# red2.net
KiCad netlist of a schematic drawn in EAGLE
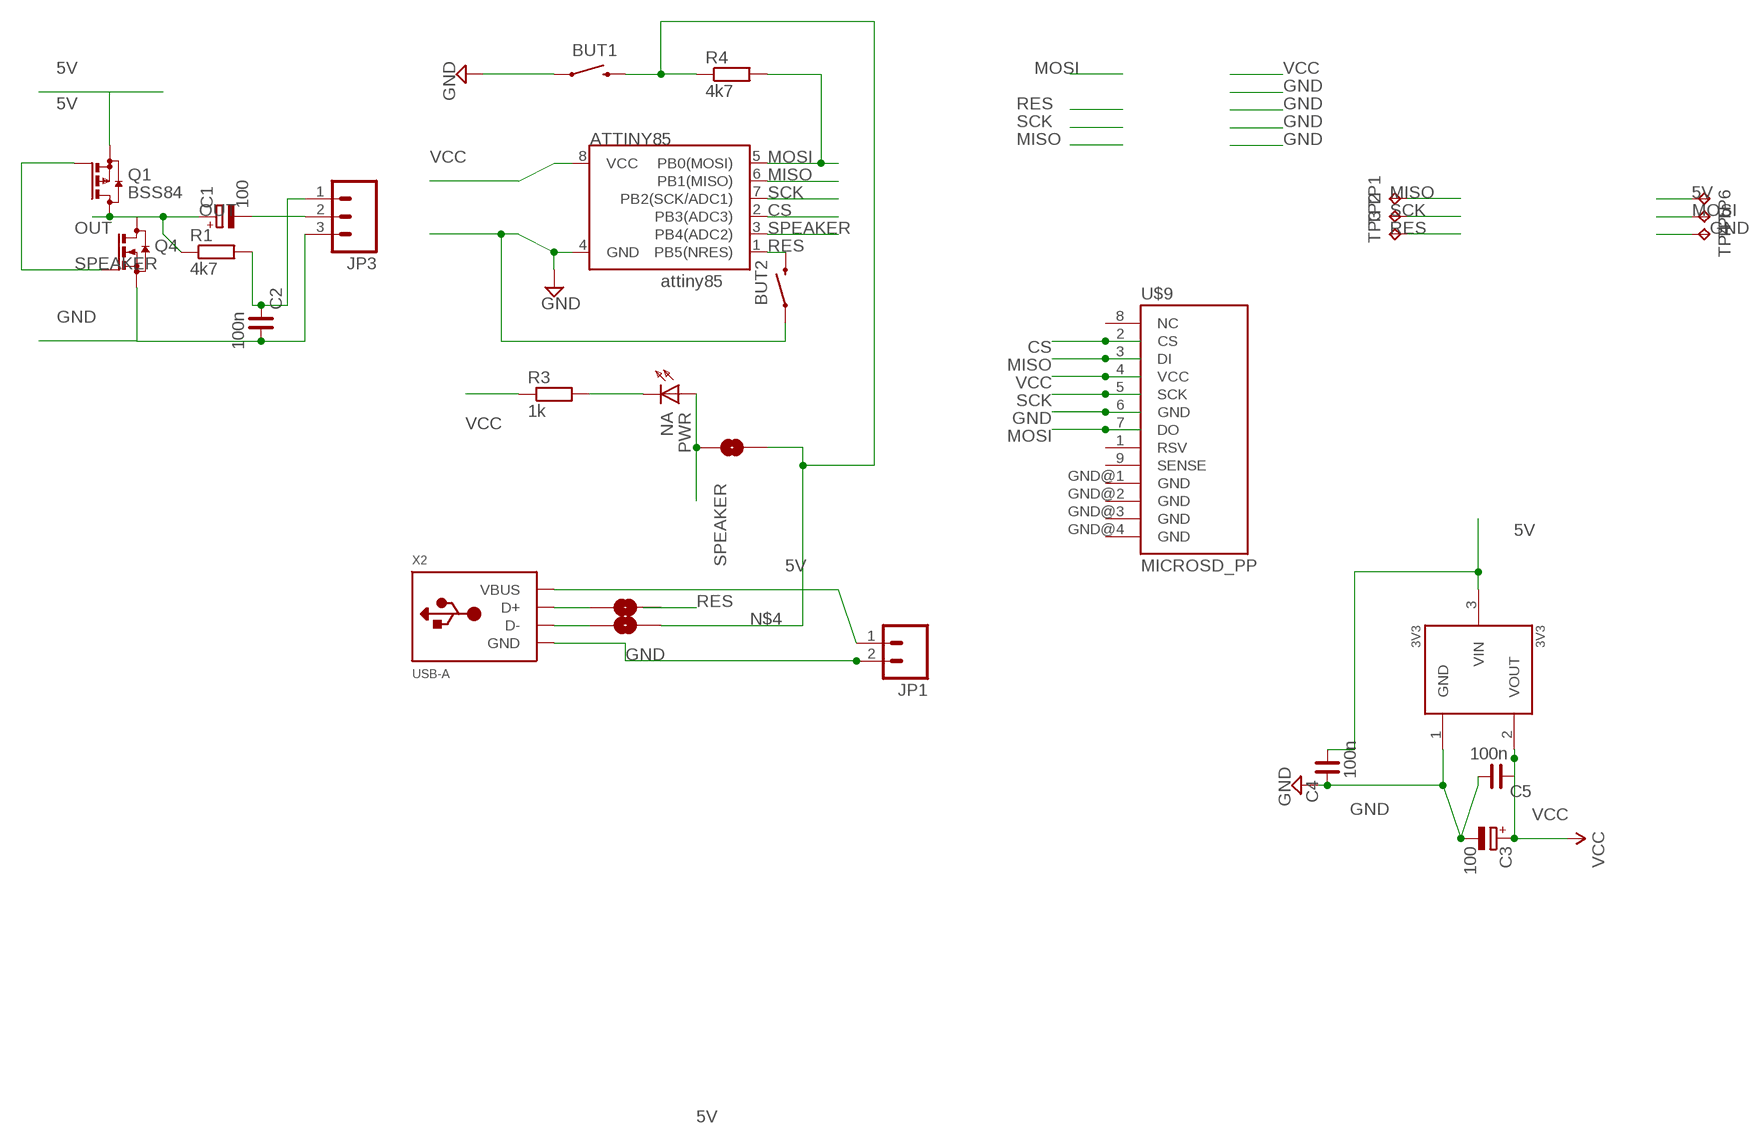
[diagram p0: schematic, sheet 1]

(export (version "E")
  (design (tool "Eeschema 10.0.6"))
  (components
    (comp (ref "3V3")
      (value "3V3")
      (footprint "eagle-import:SOT23")
      (libsource (lib "eagle-import") (part "MCP1700T"))
    )
    (comp (ref "ATTINY85")
      (value "ATTINY45")
      (footprint "eagle-import:SO08-EIAJ")
      (libsource (lib "eagle-import") (part "ATTINY45"))
    )
    (comp (ref "BUT1")
      (value "SWITCH-MOMENTARY-2-SMD-1101NE")
      (footprint "eagle-import:TACTILE-SWITCH-1101NE")
      (libsource (lib "eagle-import") (part "SWITCH-MOMENTARY-2-SMD-1101NE"))
    )
    (comp (ref "BUT2")
      (value "SWITCH-MOMENTARY-2-SMD-1101NE")
      (footprint "eagle-import:TACTILE-SWITCH-1101NE")
      (libsource (lib "eagle-import") (part "SWITCH-MOMENTARY-2-SMD-1101NE"))
    )
    (comp (ref "C1")
      (value "100")
      (footprint "eagle-import:153CLV-0605")
      (libsource (lib "eagle-import") (part "CPOL-EU153CLV-0605"))
    )
    (comp (ref "C2")
      (value "100n")
      (footprint "eagle-import:C0603")
      (libsource (lib "eagle-import") (part "C_0603"))
    )
    (comp (ref "C3")
      (value "100")
      (footprint "eagle-import:153CLV-0605")
      (libsource (lib "eagle-import") (part "CPOL-EU153CLV-0605"))
    )
    (comp (ref "C4")
      (value "100n")
      (footprint "eagle-import:C0603")
      (libsource (lib "eagle-import") (part "C_0603"))
    )
    (comp (ref "C5")
      (value "100n")
      (footprint "eagle-import:C0603")
      (libsource (lib "eagle-import") (part "C_0603"))
    )
    (comp (ref "JP1")
      (value "M02PTH")
      (footprint "eagle-import:1X02")
      (libsource (lib "eagle-import") (part "M02PTH"))
    )
    (comp (ref "JP3")
      (value "M03PTH")
      (footprint "eagle-import:1X03")
      (libsource (lib "eagle-import") (part "M03PTH"))
    )
    (comp (ref "PWR")
      (value "NA")
      (footprint "eagle-import:LED-0603")
      (libsource (lib "eagle-import") (part "LED0603DWS"))
    )
    (comp (ref "Q1")
      (value "BSS84")
      (footprint "eagle-import:SOT23")
      (libsource (lib "eagle-import") (part "BSS84"))
    )
    (comp (ref "Q4")
      (value "BSS123")
      (footprint "eagle-import:SOT23")
      (libsource (lib "eagle-import") (part "BSS123"))
    )
    (comp (ref "R1")
      (value "4k7")
      (footprint "eagle-import:R0603")
      (libsource (lib "eagle-import") (part "R-EU_R0603"))
    )
    (comp (ref "R3")
      (value "1k")
      (footprint "eagle-import:R0603")
      (libsource (lib "eagle-import") (part "R-EU_R0603"))
    )
    (comp (ref "R4")
      (value "4k7")
      (footprint "eagle-import:R0603")
      (libsource (lib "eagle-import") (part "R-EU_R0603"))
    )
    (comp (ref "SJ1")
      (value "SOLDERJUMPERNC")
      (footprint "eagle-import:SJ_2S")
      (libsource (lib "eagle-import") (part "SOLDERJUMPERNC"))
    )
    (comp (ref "SJ2")
      (value "SOLDERJUMPERNC")
      (footprint "eagle-import:SJ_2S")
      (libsource (lib "eagle-import") (part "SOLDERJUMPERNC"))
    )
    (comp (ref "SJ3")
      (value "SOLDERJUMPERNC")
      (footprint "eagle-import:SJ_2S")
      (libsource (lib "eagle-import") (part "SOLDERJUMPERNC"))
    )
    (comp (ref "TP1")
      (value "TPB1,27")
      (footprint "eagle-import:B1,27")
      (libsource (lib "eagle-import") (part "TPB1,27"))
    )
    (comp (ref "TP2")
      (value "TPB1,27")
      (footprint "eagle-import:B1,27")
      (libsource (lib "eagle-import") (part "TPB1,27"))
    )
    (comp (ref "TP3")
      (value "TPB1,27")
      (footprint "eagle-import:B1,27")
      (libsource (lib "eagle-import") (part "TPB1,27"))
    )
    (comp (ref "TP4")
      (value "TPB1,27")
      (footprint "eagle-import:B1,27")
      (libsource (lib "eagle-import") (part "TPB1,27"))
    )
    (comp (ref "TP5")
      (value "TPB1,27")
      (footprint "eagle-import:B1,27")
      (libsource (lib "eagle-import") (part "TPB1,27"))
    )
    (comp (ref "TP6")
      (value "TPB1,27")
      (footprint "eagle-import:B1,27")
      (libsource (lib "eagle-import") (part "TPB1,27"))
    )
    (comp (ref "U$9")
      (value "MICROSD_PP")
      (footprint "eagle-import:MICROSD_PP")
      (libsource (lib "eagle-import") (part "MICROSD_PP"))
    )
    (comp (ref "X2")
      (value "USB-A")
      (footprint "eagle-import:MOLEX_480371000")
      (libsource (lib "eagle-import") (part "USB-A"))
    )
  )
  (nets
    (net (code "1") (name "/5V") (class "Default")
      (node (ref "3V3") (pin "3") (pinfunction "VIN_3") (pintype "bidirectional"))
      (node (ref "C4") (pin "1") (pinfunction "1_1") (pintype "passive"))
      (node (ref "JP1") (pin "1") (pinfunction "1_1") (pintype "passive"))
      (node (ref "Q1") (pin "2") (pinfunction "S_2") (pintype "passive"))
      (node (ref "TP6") (pin "TP") (pinfunction "TP_TP") (pintype "input"))
      (node (ref "X2") (pin "1") (pinfunction "VBUS_1") (pintype "power_in"))
    )
    (net (code "2") (name "/CS") (class "Default")
      (node (ref "ATTINY85") (pin "2") (pinfunction "PB3(ADC3)_2") (pintype "bidirectional"))
      (node (ref "U$9") (pin "2") (pinfunction "CS_2") (pintype "bidirectional"))
    )
    (net (code "3") (name "/MISO") (class "Default")
      (node (ref "ATTINY85") (pin "6") (pinfunction "PB1(MISO)_6") (pintype "bidirectional"))
      (node (ref "TP1") (pin "TP") (pinfunction "TP_TP") (pintype "input"))
      (node (ref "U$9") (pin "3") (pinfunction "DI_3") (pintype "bidirectional"))
    )
    (net (code "4") (name "/MOSI") (class "Default")
      (node (ref "ATTINY85") (pin "5") (pinfunction "PB0(MOSI)_5") (pintype "bidirectional"))
      (node (ref "R4") (pin "2") (pinfunction "2_2") (pintype "passive"))
      (node (ref "TP5") (pin "TP") (pinfunction "TP_TP") (pintype "input"))
      (node (ref "U$9") (pin "7") (pinfunction "DO_7") (pintype "bidirectional"))
    )
    (net (code "5") (name "/N$4") (class "Default")
      (node (ref "BUT1") (pin "P$2") (pinfunction "2_P$2") (pintype "passive"))
      (node (ref "R4") (pin "1") (pinfunction "1_1") (pintype "passive"))
      (node (ref "SJ1") (pin "2") (pinfunction "2_2") (pintype "passive"))
      (node (ref "SJ3") (pin "2") (pinfunction "2_2") (pintype "passive"))
    )
    (net (code "6") (name "/OUT") (class "Default")
      (node (ref "C1") (pin "+") (pinfunction "+_+") (pintype "passive"))
      (node (ref "Q1") (pin "3") (pinfunction "D_3") (pintype "passive"))
      (node (ref "Q4") (pin "3") (pinfunction "D_3") (pintype "passive"))
      (node (ref "R1") (pin "1") (pinfunction "1_1") (pintype "passive"))
    )
    (net (code "7") (name "/RES") (class "Default")
      (node (ref "ATTINY85") (pin "1") (pinfunction "PB5(NRES)_1") (pintype "bidirectional"))
      (node (ref "BUT2") (pin "P$2") (pinfunction "2_P$2") (pintype "passive"))
      (node (ref "TP3") (pin "TP") (pinfunction "TP_TP") (pintype "input"))
    )
    (net (code "8") (name "/SCK") (class "Default")
      (node (ref "ATTINY85") (pin "7") (pinfunction "PB2(SCK/ADC1)_7") (pintype "bidirectional"))
      (node (ref "TP2") (pin "TP") (pinfunction "TP_TP") (pintype "input"))
      (node (ref "U$9") (pin "5") (pinfunction "SCK_5") (pintype "bidirectional"))
    )
    (net (code "9") (name "/SPEAKER") (class "Default")
      (node (ref "ATTINY85") (pin "3") (pinfunction "PB4(ADC2)_3") (pintype "bidirectional"))
      (node (ref "PWR") (pin "A") (pinfunction "A_A") (pintype "passive"))
      (node (ref "Q1") (pin "1") (pinfunction "G_1") (pintype "passive"))
      (node (ref "Q4") (pin "1") (pinfunction "G_1") (pintype "passive"))
      (node (ref "SJ1") (pin "1") (pinfunction "1_1") (pintype "passive"))
    )
    (net (code "10") (name "GND") (class "Default")
      (node (ref "3V3") (pin "1") (pinfunction "GND_1") (pintype "bidirectional"))
      (node (ref "ATTINY85") (pin "4") (pinfunction "GND_4") (pintype "bidirectional"))
      (node (ref "BUT1") (pin "P$1") (pinfunction "1_P$1") (pintype "passive"))
      (node (ref "BUT2") (pin "P$1") (pinfunction "1_P$1") (pintype "passive"))
      (node (ref "C2") (pin "1") (pinfunction "1_1") (pintype "passive"))
      (node (ref "C3") (pin "-") (pinfunction "-_-") (pintype "passive"))
      (node (ref "C4") (pin "2") (pinfunction "2_2") (pintype "passive"))
      (node (ref "C5") (pin "1") (pinfunction "1_1") (pintype "passive"))
      (node (ref "JP1") (pin "2") (pinfunction "2_2") (pintype "passive"))
      (node (ref "JP3") (pin "3") (pinfunction "3_3") (pintype "passive"))
      (node (ref "Q4") (pin "2") (pinfunction "S_2") (pintype "passive"))
      (node (ref "TP4") (pin "TP") (pinfunction "TP_TP") (pintype "input"))
      (node (ref "U$9") (pin "6") (pinfunction "GND_6") (pintype "bidirectional"))
      (node (ref "X2") (pin "4") (pinfunction "GND_4") (pintype "power_in"))
    )
    (net (code "11") (name "Net-(C1-Pad-)") (class "Default")
      (node (ref "C1") (pin "-") (pinfunction "-_-") (pintype "passive"))
      (node (ref "JP3") (pin "2") (pinfunction "2_2") (pintype "passive"))
    )
    (net (code "12") (name "Net-(C2-Pad2)") (class "Default")
      (node (ref "C2") (pin "2") (pinfunction "2_2") (pintype "passive"))
      (node (ref "JP3") (pin "1") (pinfunction "1_1") (pintype "passive"))
      (node (ref "R1") (pin "2") (pinfunction "2_2") (pintype "passive"))
    )
    (net (code "13") (name "Net-(PWR-PadC)") (class "Default")
      (node (ref "PWR") (pin "C") (pinfunction "C_C") (pintype "passive"))
      (node (ref "R3") (pin "2") (pinfunction "2_2") (pintype "passive"))
    )
    (net (code "14") (name "Net-(X2-D+)") (class "Default")
      (node (ref "SJ2") (pin "1") (pinfunction "1_1") (pintype "passive"))
      (node (ref "X2") (pin "3") (pinfunction "D+_3") (pintype "bidirectional"))
    )
    (net (code "15") (name "Net-(X2-D-)") (class "Default")
      (node (ref "SJ3") (pin "1") (pinfunction "1_1") (pintype "passive"))
      (node (ref "X2") (pin "2") (pinfunction "D-_2") (pintype "bidirectional"))
    )
    (net (code "16") (name "VCC") (class "Default")
      (node (ref "3V3") (pin "2") (pinfunction "VOUT_2") (pintype "bidirectional"))
      (node (ref "ATTINY85") (pin "8") (pinfunction "VCC_8") (pintype "bidirectional"))
      (node (ref "C3") (pin "+") (pinfunction "+_+") (pintype "passive"))
      (node (ref "C5") (pin "2") (pinfunction "2_2") (pintype "passive"))
      (node (ref "R3") (pin "1") (pinfunction "1_1") (pintype "passive"))
      (node (ref "U$9") (pin "4") (pinfunction "VCC_4") (pintype "bidirectional"))
    )
    (net (code "17") (name "unconnected-(SJ2-Pad2)") (class "Default")
      (node (ref "SJ2") (pin "2") (pinfunction "2_2") (pintype "passive"))
    )
    (net (code "18") (name "unconnected-(U$9-GND-PadGND@1)") (class "Default")
      (node (ref "U$9") (pin "GND@1") (pinfunction "GND_GND@1") (pintype "bidirectional"))
    )
    (net (code "19") (name "unconnected-(U$9-GND-PadGND@2)") (class "Default")
      (node (ref "U$9") (pin "GND@2") (pinfunction "GND_GND@2") (pintype "bidirectional"))
    )
    (net (code "20") (name "unconnected-(U$9-GND-PadGND@3)") (class "Default")
      (node (ref "U$9") (pin "GND@3") (pinfunction "GND_GND@3") (pintype "bidirectional"))
    )
    (net (code "21") (name "unconnected-(U$9-GND-PadGND@4)") (class "Default")
      (node (ref "U$9") (pin "GND@4") (pinfunction "GND_GND@4") (pintype "bidirectional"))
    )
    (net (code "22") (name "unconnected-(U$9-NC-Pad8)") (class "Default")
      (node (ref "U$9") (pin "8") (pinfunction "NC_8") (pintype "bidirectional"))
    )
    (net (code "23") (name "unconnected-(U$9-RSV-Pad1)") (class "Default")
      (node (ref "U$9") (pin "1") (pinfunction "RSV_1") (pintype "bidirectional"))
    )
    (net (code "24") (name "unconnected-(U$9-SENSE-Pad9)") (class "Default")
      (node (ref "U$9") (pin "9") (pinfunction "SENSE_9") (pintype "bidirectional"))
    )
  )
)
